# as14120_usb.net
KiCad netlist of a schematic drawn in Altium Designer
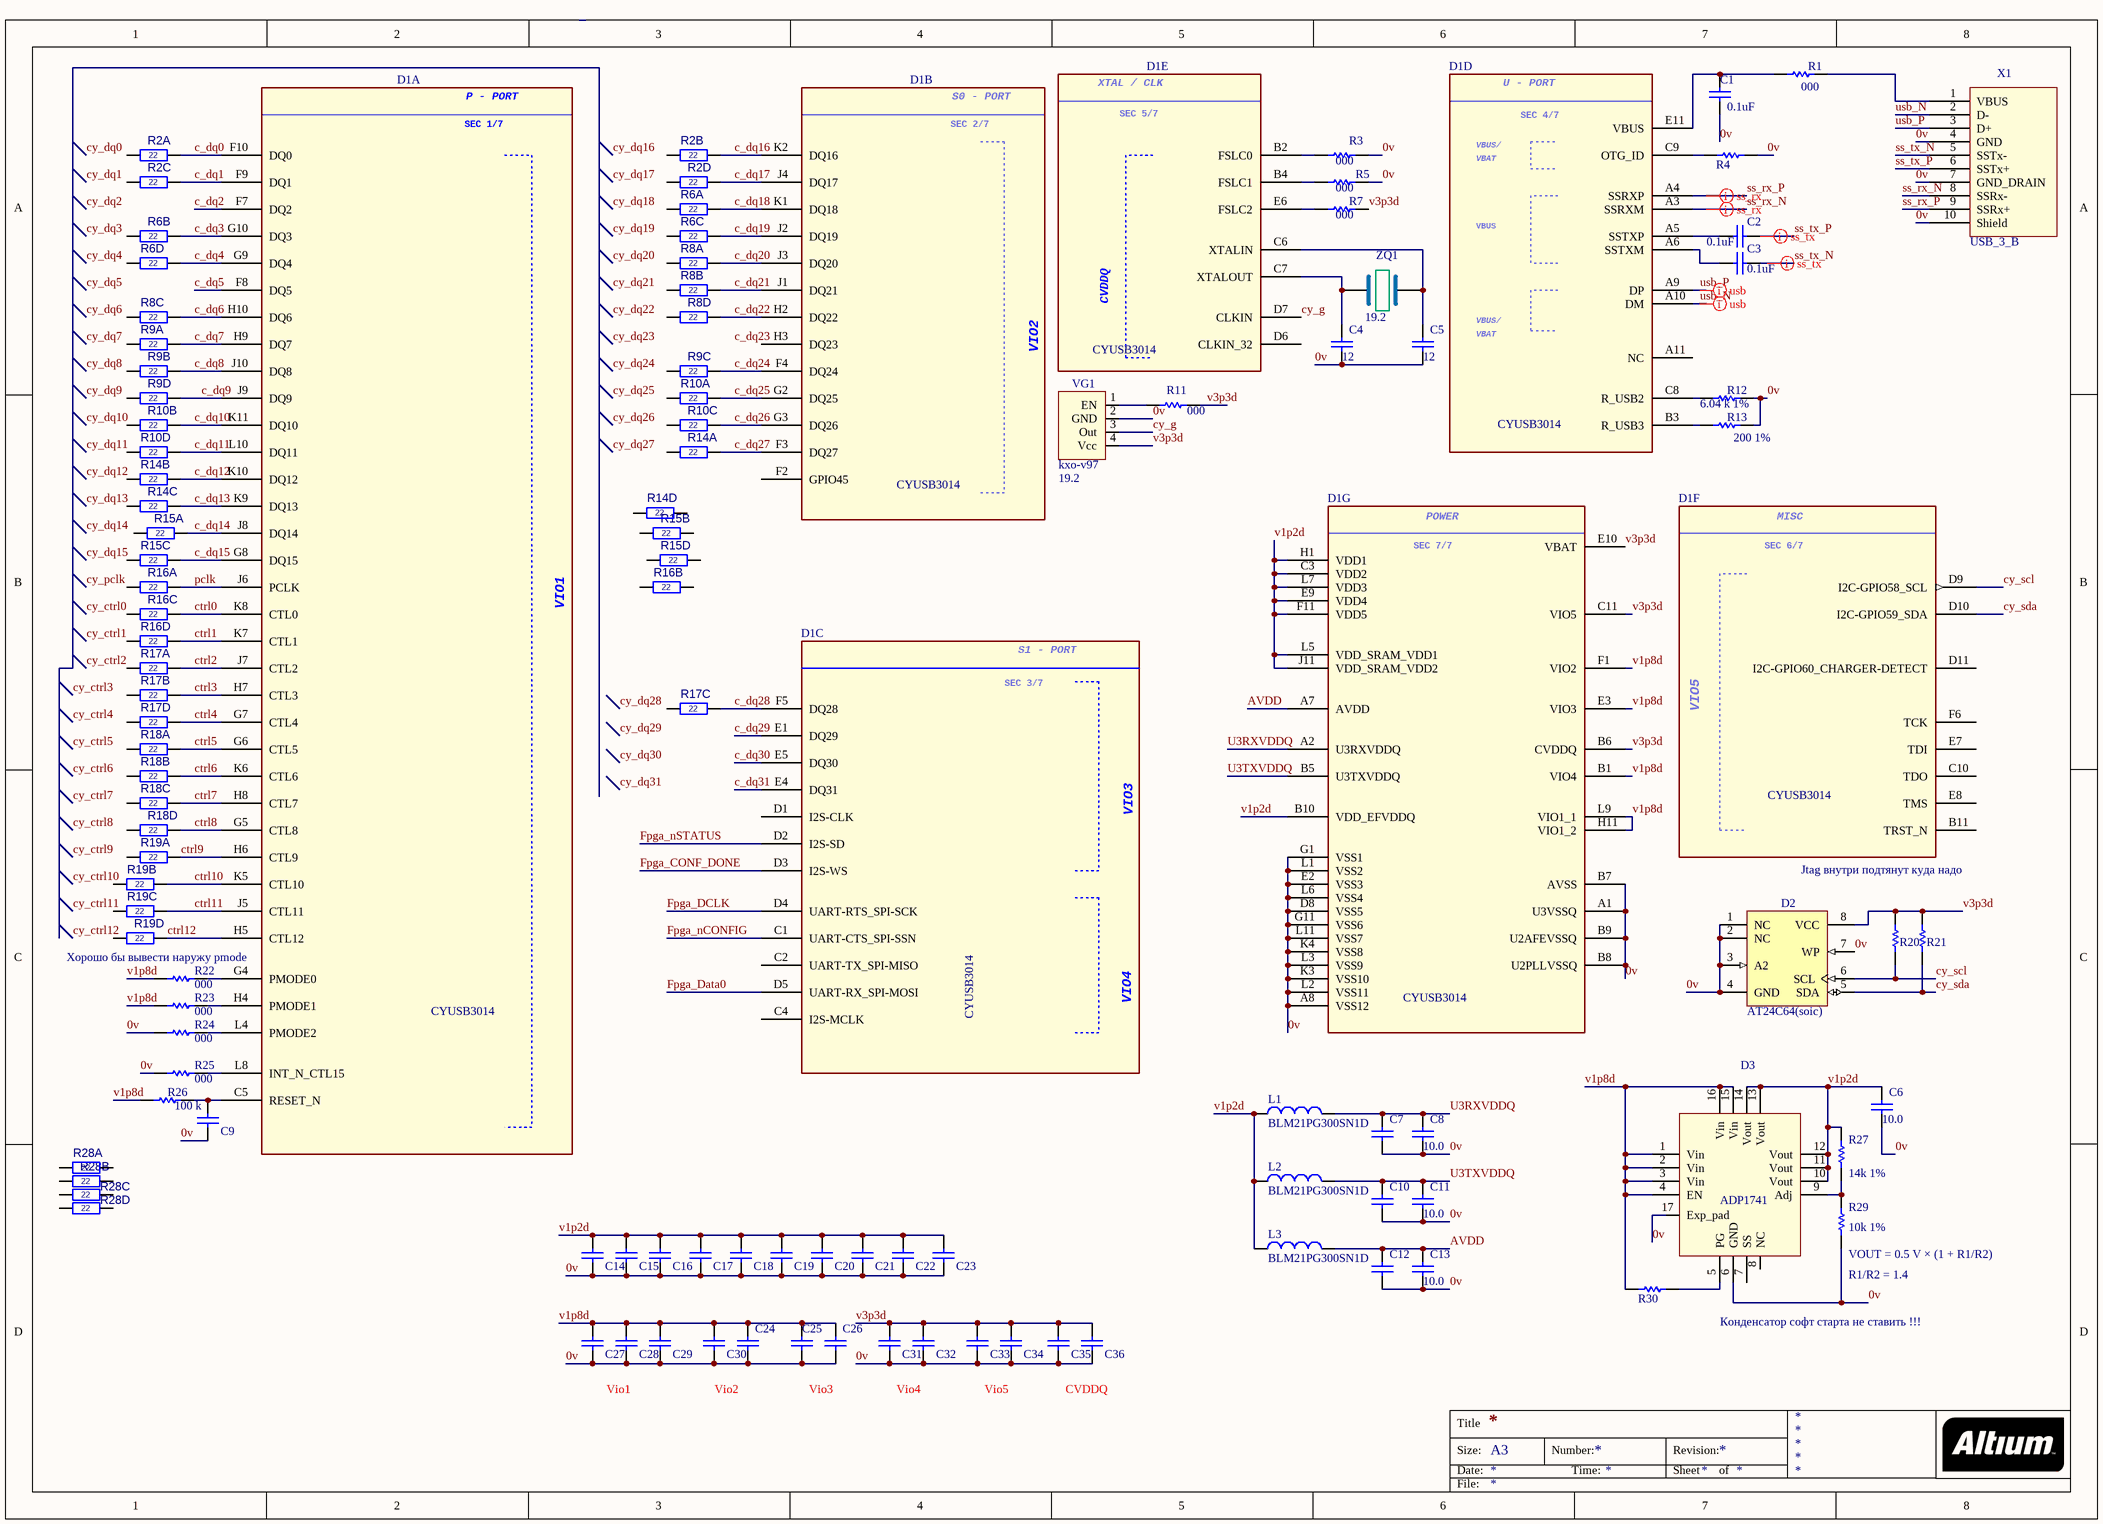
[diagram p0: as14120_usb.SchDoc]

(export (version "E")
  (design (tool "Eeschema 10.0.6"))
  (components
    (comp (ref "C1")
      (value "0.1uF")
      (footprint "CAPC0402(1005)60_M")
      (description "CAP 1uF 10V ±20% 0402 (1005 Metric) Thickness 0.6mm SMD")
      (fields (field (name "TOLERANCE") "±20%") (field (name "Comment") "CAP 1uF 10V 0402(1005)"))
      (libsource (lib "as14120") (part "CAP_0402"))
    )
    (comp (ref "C2")
      (value "0.1uF")
      (footprint "CAPC0402(1005)60_M")
      (description "CAP 1uF 10V ±20% 0402 (1005 Metric) Thickness 0.6mm SMD")
      (fields (field (name "TOLERANCE") "±20%") (field (name "Comment") "CAP 1uF 10V 0402(1005)"))
      (libsource (lib "as14120") (part "CAP_0402"))
    )
    (comp (ref "C3")
      (value "0.1uF")
      (footprint "CAPC0402(1005)60_M")
      (description "CAP 1uF 10V ±20% 0402 (1005 Metric) Thickness 0.6mm SMD")
      (fields (field (name "TOLERANCE") "±20%") (field (name "Comment") "CAP 1uF 10V 0402(1005)"))
      (libsource (lib "as14120") (part "CAP_0402"))
    )
    (comp (ref "C4")
      (value "12")
      (footprint "CAPC0805(2012)100_N")
      (fields (field (name "Comment") "CAP_0805"))
      (libsource (lib "as14120") (part "CAP_0805"))
    )
    (comp (ref "C5")
      (value "12")
      (footprint "CAPC0805(2012)100_N")
      (fields (field (name "Comment") "CAP_0805"))
      (libsource (lib "as14120") (part "CAP_0805"))
    )
    (comp (ref "C6")
      (value "10.0")
      (footprint "CAPC0805(2012)100_N")
      (fields (field (name "Comment") "CAP_0805"))
      (libsource (lib "as14120") (part "CAP_0805"))
    )
    (comp (ref "C7")
      (value "CAP 1uF 10V 0402(1005)")
      (footprint "CAPC0402(1005)60_M")
      (description "CAP 1uF 10V ±20% 0402 (1005 Metric) Thickness 0.6mm SMD")
      (fields (field (name "TOLERANCE") "±20%"))
      (libsource (lib "as14120") (part "CAP_0402"))
    )
    (comp (ref "C8")
      (value "10.0")
      (footprint "CAPC0805(2012)100_N")
      (fields (field (name "Comment") "CAP_0805"))
      (libsource (lib "as14120") (part "CAP_0805"))
    )
    (comp (ref "C9")
      (value "CAP 1uF 10V 0402(1005)")
      (footprint "CAPC0402(1005)60_M")
      (description "CAP 1uF 10V ±20% 0402 (1005 Metric) Thickness 0.6mm SMD")
      (fields (field (name "TOLERANCE") "±20%"))
      (libsource (lib "as14120") (part "CAP_0402"))
    )
    (comp (ref "C10")
      (value "CAP 1uF 10V 0402(1005)")
      (footprint "CAPC0402(1005)60_M")
      (description "CAP 1uF 10V ±20% 0402 (1005 Metric) Thickness 0.6mm SMD")
      (fields (field (name "TOLERANCE") "±20%"))
      (libsource (lib "as14120") (part "CAP_0402"))
    )
    (comp (ref "C11")
      (value "10.0")
      (footprint "CAPC0805(2012)100_N")
      (fields (field (name "Comment") "CAP_0805"))
      (libsource (lib "as14120") (part "CAP_0805"))
    )
    (comp (ref "C12")
      (value "CAP 1uF 10V 0402(1005)")
      (footprint "CAPC0402(1005)60_M")
      (description "CAP 1uF 10V ±20% 0402 (1005 Metric) Thickness 0.6mm SMD")
      (fields (field (name "TOLERANCE") "±20%"))
      (libsource (lib "as14120") (part "CAP_0402"))
    )
    (comp (ref "C13")
      (value "10.0")
      (footprint "CAPC0805(2012)100_N")
      (fields (field (name "Comment") "CAP_0805"))
      (libsource (lib "as14120") (part "CAP_0805"))
    )
    (comp (ref "C14")
      (value "CAP 1uF 10V 0402(1005)")
      (footprint "CAPC0402(1005)60_M")
      (description "CAP 1uF 10V ±20% 0402 (1005 Metric) Thickness 0.6mm SMD")
      (fields (field (name "TOLERANCE") "±20%"))
      (libsource (lib "as14120") (part "CAP_0402"))
    )
    (comp (ref "C15")
      (value "CAP 1uF 10V 0402(1005)")
      (footprint "CAPC0402(1005)60_M")
      (description "CAP 1uF 10V ±20% 0402 (1005 Metric) Thickness 0.6mm SMD")
      (fields (field (name "TOLERANCE") "±20%"))
      (libsource (lib "as14120") (part "CAP_0402"))
    )
    (comp (ref "C16")
      (value "CAP 1uF 10V 0402(1005)")
      (footprint "CAPC0402(1005)60_M")
      (description "CAP 1uF 10V ±20% 0402 (1005 Metric) Thickness 0.6mm SMD")
      (fields (field (name "TOLERANCE") "±20%"))
      (libsource (lib "as14120") (part "CAP_0402"))
    )
    (comp (ref "C17")
      (value "CAP 1uF 10V 0402(1005)")
      (footprint "CAPC0402(1005)60_M")
      (description "CAP 1uF 10V ±20% 0402 (1005 Metric) Thickness 0.6mm SMD")
      (fields (field (name "TOLERANCE") "±20%"))
      (libsource (lib "as14120") (part "CAP_0402"))
    )
    (comp (ref "C18")
      (value "CAP 1uF 10V 0402(1005)")
      (footprint "CAPC0402(1005)60_M")
      (description "CAP 1uF 10V ±20% 0402 (1005 Metric) Thickness 0.6mm SMD")
      (fields (field (name "TOLERANCE") "±20%"))
      (libsource (lib "as14120") (part "CAP_0402"))
    )
    (comp (ref "C19")
      (value "CAP 1uF 10V 0402(1005)")
      (footprint "CAPC0402(1005)60_M")
      (description "CAP 1uF 10V ±20% 0402 (1005 Metric) Thickness 0.6mm SMD")
      (fields (field (name "TOLERANCE") "±20%"))
      (libsource (lib "as14120") (part "CAP_0402"))
    )
    (comp (ref "C20")
      (value "CAP 1uF 10V 0402(1005)")
      (footprint "CAPC0402(1005)60_M")
      (description "CAP 1uF 10V ±20% 0402 (1005 Metric) Thickness 0.6mm SMD")
      (fields (field (name "TOLERANCE") "±20%"))
      (libsource (lib "as14120") (part "CAP_0402"))
    )
    (comp (ref "C21")
      (value "CAP 1uF 10V 0402(1005)")
      (footprint "CAPC0402(1005)60_M")
      (description "CAP 1uF 10V ±20% 0402 (1005 Metric) Thickness 0.6mm SMD")
      (fields (field (name "TOLERANCE") "±20%"))
      (libsource (lib "as14120") (part "CAP_0402"))
    )
    (comp (ref "C22")
      (value "CAP 1uF 10V 0402(1005)")
      (footprint "CAPC0402(1005)60_M")
      (description "CAP 1uF 10V ±20% 0402 (1005 Metric) Thickness 0.6mm SMD")
      (fields (field (name "TOLERANCE") "±20%"))
      (libsource (lib "as14120") (part "CAP_0402"))
    )
    (comp (ref "C23")
      (value "CAP 1uF 10V 0402(1005)")
      (footprint "CAPC0402(1005)60_M")
      (description "CAP 1uF 10V ±20% 0402 (1005 Metric) Thickness 0.6mm SMD")
      (fields (field (name "TOLERANCE") "±20%"))
      (libsource (lib "as14120") (part "CAP_0402"))
    )
    (comp (ref "C24")
      (value "CAP 1uF 10V 0402(1005)")
      (footprint "CAPC0402(1005)60_M")
      (description "CAP 1uF 10V ±20% 0402 (1005 Metric) Thickness 0.6mm SMD")
      (fields (field (name "TOLERANCE") "±20%"))
      (libsource (lib "as14120") (part "CAP_0402"))
    )
    (comp (ref "C25")
      (value "CAP 1uF 10V 0402(1005)")
      (footprint "CAPC0402(1005)60_M")
      (description "CAP 1uF 10V ±20% 0402 (1005 Metric) Thickness 0.6mm SMD")
      (fields (field (name "TOLERANCE") "±20%"))
      (libsource (lib "as14120") (part "CAP_0402"))
    )
    (comp (ref "C26")
      (value "CAP 1uF 10V 0402(1005)")
      (footprint "CAPC0402(1005)60_M")
      (description "CAP 1uF 10V ±20% 0402 (1005 Metric) Thickness 0.6mm SMD")
      (fields (field (name "TOLERANCE") "±20%"))
      (libsource (lib "as14120") (part "CAP_0402"))
    )
    (comp (ref "C27")
      (value "CAP 1uF 10V 0402(1005)")
      (footprint "CAPC0402(1005)60_M")
      (description "CAP 1uF 10V ±20% 0402 (1005 Metric) Thickness 0.6mm SMD")
      (fields (field (name "TOLERANCE") "±20%"))
      (libsource (lib "as14120") (part "CAP_0402"))
    )
    (comp (ref "C28")
      (value "CAP 1uF 10V 0402(1005)")
      (footprint "CAPC0402(1005)60_M")
      (description "CAP 1uF 10V ±20% 0402 (1005 Metric) Thickness 0.6mm SMD")
      (fields (field (name "TOLERANCE") "±20%"))
      (libsource (lib "as14120") (part "CAP_0402"))
    )
    (comp (ref "C29")
      (value "CAP 1uF 10V 0402(1005)")
      (footprint "CAPC0402(1005)60_M")
      (description "CAP 1uF 10V ±20% 0402 (1005 Metric) Thickness 0.6mm SMD")
      (fields (field (name "TOLERANCE") "±20%"))
      (libsource (lib "as14120") (part "CAP_0402"))
    )
    (comp (ref "C30")
      (value "CAP 1uF 10V 0402(1005)")
      (footprint "CAPC0402(1005)60_M")
      (description "CAP 1uF 10V ±20% 0402 (1005 Metric) Thickness 0.6mm SMD")
      (fields (field (name "TOLERANCE") "±20%"))
      (libsource (lib "as14120") (part "CAP_0402"))
    )
    (comp (ref "C31")
      (value "CAP 1uF 10V 0402(1005)")
      (footprint "CAPC0402(1005)60_M")
      (description "CAP 1uF 10V ±20% 0402 (1005 Metric) Thickness 0.6mm SMD")
      (fields (field (name "TOLERANCE") "±20%"))
      (libsource (lib "as14120") (part "CAP_0402"))
    )
    (comp (ref "C32")
      (value "CAP 1uF 10V 0402(1005)")
      (footprint "CAPC0402(1005)60_M")
      (description "CAP 1uF 10V ±20% 0402 (1005 Metric) Thickness 0.6mm SMD")
      (fields (field (name "TOLERANCE") "±20%"))
      (libsource (lib "as14120") (part "CAP_0402"))
    )
    (comp (ref "C33")
      (value "CAP 1uF 10V 0402(1005)")
      (footprint "CAPC0402(1005)60_M")
      (description "CAP 1uF 10V ±20% 0402 (1005 Metric) Thickness 0.6mm SMD")
      (fields (field (name "TOLERANCE") "±20%"))
      (libsource (lib "as14120") (part "CAP_0402"))
    )
    (comp (ref "C34")
      (value "CAP 1uF 10V 0402(1005)")
      (footprint "CAPC0402(1005)60_M")
      (description "CAP 1uF 10V ±20% 0402 (1005 Metric) Thickness 0.6mm SMD")
      (fields (field (name "TOLERANCE") "±20%"))
      (libsource (lib "as14120") (part "CAP_0402"))
    )
    (comp (ref "C35")
      (value "CAP 1uF 10V 0402(1005)")
      (footprint "CAPC0402(1005)60_M")
      (description "CAP 1uF 10V ±20% 0402 (1005 Metric) Thickness 0.6mm SMD")
      (fields (field (name "TOLERANCE") "±20%"))
      (libsource (lib "as14120") (part "CAP_0402"))
    )
    (comp (ref "C36")
      (value "CAP 1uF 10V 0402(1005)")
      (footprint "CAPC0402(1005)60_M")
      (description "CAP 1uF 10V ±20% 0402 (1005 Metric) Thickness 0.6mm SMD")
      (fields (field (name "TOLERANCE") "±20%"))
      (libsource (lib "as14120") (part "CAP_0402"))
    )
    (comp (ref "D1")
      (value "CYUSB3014")
      (footprint "BGA121C80P11X11")
      (libsource (lib "as14120") (part "CYUSB3014-BZXC"))
    )
    (comp (ref "D2")
      (value "AT24C64(soic)")
      (footprint "8S1_N")
      (libsource (lib "Atmel Serial EEPROM") (part "AT24C08BN-SP25-T"))
    )
    (comp (ref "D3") (value "ADP1741") (footprint "CP-16-4_N") (libsource (lib "as14120") (part "ADP1741")))
    (comp (ref "L1")
      (value "BLM21PG300SN1D")
      (footprint "CAPC0805(2012)100_N")
      (libsource (lib "as14120") (part "Ferrite_beat"))
    )
    (comp (ref "L2")
      (value "BLM21PG300SN1D")
      (footprint "CAPC0805(2012)100_N")
      (libsource (lib "as14120") (part "Ferrite_beat"))
    )
    (comp (ref "L3")
      (value "BLM21PG300SN1D")
      (footprint "CAPC0805(2012)100_N")
      (libsource (lib "as14120") (part "Ferrite_beat"))
    )
    (comp (ref "R1")
      (value "000")
      (footprint "RESC0805(2012)_L")
      (description "1K 0.125W 1% 0805 (2012 Metric)  SMD")
      (fields (field (name "TOLERANCE") "1 %") (field (name "POWER") "0.125 W"))
      (libsource (lib "as14120") (part "RES_0805"))
    )
    (comp (ref "R2")
      (value "22")
      (footprint "CAY16")
      (description "RES_CAY16")
      (libsource (lib "") (part "RES_CAY16_10"))
    )
    (comp (ref "R3")
      (value "000")
      (footprint "RESC0603(1608)_L")
      (description "1K 0.1W 5% 0603 (1608 Metric)  SMD")
      (fields (field (name "TOLERANCE") "5 %") (field (name "POWER") "0.1 W"))
      (libsource (lib "as14120") (part "RES_0603"))
    )
    (comp (ref "R4")
      (value "???")
      (footprint "RESC0603(1608)_L")
      (description "1K 0.1W 5% 0603 (1608 Metric)  SMD")
      (fields (field (name "TOLERANCE") "5 %") (field (name "POWER") "0.1 W"))
      (libsource (lib "as14120") (part "RES_0603"))
    )
    (comp (ref "R5")
      (value "000")
      (footprint "RESC0603(1608)_L")
      (description "1K 0.1W 5% 0603 (1608 Metric)  SMD")
      (fields (field (name "TOLERANCE") "5 %") (field (name "POWER") "0.1 W"))
      (libsource (lib "as14120") (part "RES_0603"))
    )
    (comp (ref "R6")
      (value "22")
      (footprint "CAY16")
      (description "RES_CAY16")
      (libsource (lib "alexsb") (part "RES_CAY16"))
    )
    (comp (ref "R7")
      (value "000")
      (footprint "RESC0603(1608)_L")
      (description "1K 0.1W 5% 0603 (1608 Metric)  SMD")
      (fields (field (name "TOLERANCE") "5 %") (field (name "POWER") "0.1 W"))
      (libsource (lib "as14120") (part "RES_0603"))
    )
    (comp (ref "R8")
      (value "22")
      (footprint "CAY16")
      (description "RES_CAY16")
      (libsource (lib "") (part "RES_CAY16_4"))
    )
    (comp (ref "R9")
      (value "22")
      (footprint "CAY16")
      (description "RES_CAY16")
      (libsource (lib "alexsb") (part "RES_CAY16"))
    )
    (comp (ref "R10")
      (value "22")
      (footprint "CAY16")
      (description "RES_CAY16")
      (libsource (lib "") (part "RES_CAY16_5"))
    )
    (comp (ref "R11")
      (value "000")
      (footprint "RESC0603(1608)_L")
      (description "1K 0.1W 5% 0603 (1608 Metric)  SMD")
      (fields (field (name "TOLERANCE") "5 %") (field (name "POWER") "0.1 W"))
      (libsource (lib "as14120") (part "RES_0603"))
    )
    (comp (ref "R12")
      (value "6.04 k 1%")
      (footprint "RESC0805(2012)_L")
      (description "1K 0.125W 1% 0805 (2012 Metric)  SMD")
      (fields (field (name "TOLERANCE") "1 %") (field (name "POWER") "0.125 W"))
      (libsource (lib "as14120") (part "RES_0805"))
    )
    (comp (ref "R13")
      (value "200 1%")
      (footprint "RESC0805(2012)_L")
      (description "1K 0.125W 1% 0805 (2012 Metric)  SMD")
      (fields (field (name "TOLERANCE") "1 %") (field (name "POWER") "0.125 W"))
      (libsource (lib "as14120") (part "RES_0805"))
    )
    (comp (ref "R14")
      (value "22")
      (footprint "CAY16")
      (description "RES_CAY16")
      (libsource (lib "") (part "RES_CAY16_8"))
    )
    (comp (ref "R15")
      (value "22")
      (footprint "CAY16")
      (description "RES_CAY16")
      (libsource (lib "") (part "RES_CAY16_1"))
    )
    (comp (ref "R16")
      (value "22")
      (footprint "CAY16")
      (description "RES_CAY16")
      (libsource (lib "") (part "RES_CAY16_5"))
    )
    (comp (ref "R17")
      (value "22")
      (footprint "CAY16")
      (description "RES_CAY16")
      (libsource (lib "") (part "RES_CAY16_7"))
    )
    (comp (ref "R18")
      (value "22")
      (footprint "CAY16")
      (description "RES_CAY16")
      (libsource (lib "") (part "RES_CAY16_3"))
    )
    (comp (ref "R19")
      (value "22")
      (footprint "CAY16")
      (description "RES_CAY16")
      (libsource (lib "alexsb") (part "RES_CAY16"))
    )
    (comp (ref "R20")
      (value "1K 5% 0603(1608)")
      (footprint "RESC0603(1608)_L")
      (description "1K 0.1W 5% 0603 (1608 Metric)  SMD")
      (fields (field (name "TOLERANCE") "5 %") (field (name "POWER") "0.1 W"))
      (libsource (lib "as14120") (part "RES_0603"))
    )
    (comp (ref "R21")
      (value "1K 5% 0603(1608)")
      (footprint "RESC0603(1608)_L")
      (description "1K 0.1W 5% 0603 (1608 Metric)  SMD")
      (fields (field (name "TOLERANCE") "5 %") (field (name "POWER") "0.1 W"))
      (libsource (lib "as14120") (part "RES_0603"))
    )
    (comp (ref "R22")
      (value "000")
      (footprint "RESC0603(1608)_L")
      (description "1K 0.1W 5% 0603 (1608 Metric)  SMD")
      (fields (field (name "TOLERANCE") "5 %") (field (name "POWER") "0.1 W"))
      (libsource (lib "as14120") (part "RES_0603"))
    )
    (comp (ref "R23")
      (value "000")
      (footprint "RESC0603(1608)_L")
      (description "1K 0.1W 5% 0603 (1608 Metric)  SMD")
      (fields (field (name "TOLERANCE") "5 %") (field (name "POWER") "0.1 W"))
      (libsource (lib "as14120") (part "RES_0603"))
    )
    (comp (ref "R24")
      (value "000")
      (footprint "RESC0603(1608)_L")
      (description "1K 0.1W 5% 0603 (1608 Metric)  SMD")
      (fields (field (name "TOLERANCE") "5 %") (field (name "POWER") "0.1 W"))
      (libsource (lib "as14120") (part "RES_0603"))
    )
    (comp (ref "R25")
      (value "000")
      (footprint "RESC0603(1608)_L")
      (description "1K 0.1W 5% 0603 (1608 Metric)  SMD")
      (fields (field (name "TOLERANCE") "5 %") (field (name "POWER") "0.1 W"))
      (libsource (lib "as14120") (part "RES_0603"))
    )
    (comp (ref "R26")
      (value "100 k")
      (footprint "RESC0603(1608)_L")
      (description "1K 0.1W 5% 0603 (1608 Metric)  SMD")
      (fields (field (name "TOLERANCE") "5 %") (field (name "POWER") "0.1 W"))
      (libsource (lib "as14120") (part "RES_0603"))
    )
    (comp (ref "R27")
      (value "14k 1%")
      (footprint "RESC0805(2012)_L")
      (description "1K 0.125W 1% 0805 (2012 Metric)  SMD")
      (fields (field (name "TOLERANCE") "1 %") (field (name "POWER") "0.125 W"))
      (libsource (lib "as14120") (part "RES_0805"))
    )
    (comp (ref "R28")
      (value "22")
      (footprint "CAY16")
      (description "RES_CAY16")
      (libsource (lib "") (part "RES_CAY16_1"))
    )
    (comp (ref "R29")
      (value "10k 1%")
      (footprint "RESC0805(2012)_L")
      (description "1K 0.125W 1% 0805 (2012 Metric)  SMD")
      (fields (field (name "TOLERANCE") "1 %") (field (name "POWER") "0.125 W"))
      (libsource (lib "as14120") (part "RES_0805"))
    )
    (comp (ref "R30")
      (value "1K 5% 0603(1608)")
      (footprint "RESC0603(1608)_L")
      (description "1K 0.1W 5% 0603 (1608 Metric)  SMD")
      (fields (field (name "TOLERANCE") "5 %") (field (name "POWER") "0.1 W"))
      (libsource (lib "as14120") (part "RES_0603"))
    )
    (comp (ref "VG1")
      (value "kxo-v97")
      (footprint "kxo-v97")
      (fields (field (name "ALTIUM_VALUE") "19.2"))
      (libsource (lib "as14120") (part "kxo-v97"))
    )
    (comp (ref "X1") (value "USB_3_B") (footprint "USB3_B") (libsource (lib "as14120") (part "USB_3_B")))
    (comp (ref "ZQ1")
      (value "19.2")
      (footprint "BCY-W2/E4.7")
      (fields (field (name "Comment") "Resonator"))
      (libsource (lib "as14120") (part "Resonator"))
    )
  )
  (nets
    (net (code "1") (name "/0v") (class "Default")
      (node (ref "C1") (pin "2") (pinfunction "2_2") (pintype "passive"))
      (node (ref "C10") (pin "1") (pinfunction "1_1") (pintype "passive"))
      (node (ref "C11") (pin "1") (pinfunction "1_1") (pintype "passive"))
      (node (ref "C12") (pin "1") (pinfunction "1_1") (pintype "passive"))
      (node (ref "C13") (pin "1") (pinfunction "1_1") (pintype "passive"))
      (node (ref "C14") (pin "1") (pinfunction "1_1") (pintype "passive"))
      (node (ref "C15") (pin "1") (pinfunction "1_1") (pintype "passive"))
      (node (ref "C16") (pin "1") (pinfunction "1_1") (pintype "passive"))
      (node (ref "C17") (pin "1") (pinfunction "1_1") (pintype "passive"))
      (node (ref "C18") (pin "1") (pinfunction "1_1") (pintype "passive"))
      (node (ref "C19") (pin "1") (pinfunction "1_1") (pintype "passive"))
      (node (ref "C20") (pin "1") (pinfunction "1_1") (pintype "passive"))
      (node (ref "C21") (pin "1") (pinfunction "1_1") (pintype "passive"))
      (node (ref "C22") (pin "1") (pinfunction "1_1") (pintype "passive"))
      (node (ref "C23") (pin "1") (pinfunction "1_1") (pintype "passive"))
      (node (ref "C24") (pin "1") (pinfunction "1_1") (pintype "passive"))
      (node (ref "C25") (pin "1") (pinfunction "1_1") (pintype "passive"))
      (node (ref "C26") (pin "1") (pinfunction "1_1") (pintype "passive"))
      (node (ref "C27") (pin "1") (pinfunction "1_1") (pintype "passive"))
      (node (ref "C28") (pin "1") (pinfunction "1_1") (pintype "passive"))
      (node (ref "C29") (pin "1") (pinfunction "1_1") (pintype "passive"))
      (node (ref "C30") (pin "1") (pinfunction "1_1") (pintype "passive"))
      (node (ref "C31") (pin "1") (pinfunction "1_1") (pintype "passive"))
      (node (ref "C32") (pin "1") (pinfunction "1_1") (pintype "passive"))
      (node (ref "C33") (pin "1") (pinfunction "1_1") (pintype "passive"))
      (node (ref "C34") (pin "1") (pinfunction "1_1") (pintype "passive"))
      (node (ref "C35") (pin "1") (pinfunction "1_1") (pintype "passive"))
      (node (ref "C36") (pin "1") (pinfunction "1_1") (pintype "passive"))
      (node (ref "C4") (pin "1") (pinfunction "1_1") (pintype "passive"))
      (node (ref "C5") (pin "1") (pinfunction "1_1") (pintype "passive"))
      (node (ref "C6") (pin "1") (pinfunction "1_1") (pintype "passive"))
      (node (ref "C7") (pin "1") (pinfunction "1_1") (pintype "passive"))
      (node (ref "C8") (pin "1") (pinfunction "1_1") (pintype "passive"))
      (node (ref "C9") (pin "1") (pinfunction "1_1") (pintype "passive"))
      (node (ref "D1") (pin "A1") (pinfunction "U3VSSQ_A1") (pintype "passive"))
      (node (ref "D1") (pin "A8") (pinfunction "VSS12_A8") (pintype "passive"))
      (node (ref "D1") (pin "B7") (pinfunction "AVSS_B7") (pintype "passive"))
      (node (ref "D1") (pin "B8") (pinfunction "U2PLLVSSQ_B8") (pintype "passive"))
      (node (ref "D1") (pin "B9") (pinfunction "U2AFEVSSQ_B9") (pintype "passive"))
      (node (ref "D1") (pin "D8") (pinfunction "VSS5_D8") (pintype "passive"))
      (node (ref "D1") (pin "E2") (pinfunction "VSS3_E2") (pintype "passive"))
      (node (ref "D1") (pin "G1") (pinfunction "VSS1_G1") (pintype "passive"))
      (node (ref "D1") (pin "G11") (pinfunction "VSS6_G11") (pintype "passive"))
      (node (ref "D1") (pin "K3") (pinfunction "VSS10_K3") (pintype "passive"))
      (node (ref "D1") (pin "K4") (pinfunction "VSS8_K4") (pintype "passive"))
      (node (ref "D1") (pin "L1") (pinfunction "VSS2_L1") (pintype "passive"))
      (node (ref "D1") (pin "L11") (pinfunction "VSS7_L11") (pintype "passive"))
      (node (ref "D1") (pin "L2") (pinfunction "VSS11_L2") (pintype "passive"))
      (node (ref "D1") (pin "L3") (pinfunction "VSS9_L3") (pintype "passive"))
      (node (ref "D1") (pin "L6") (pinfunction "VSS4_L6") (pintype "passive"))
      (node (ref "D2") (pin "1") (pinfunction "NC_1") (pintype "passive"))
      (node (ref "D2") (pin "2") (pinfunction "NC_2") (pintype "passive"))
      (node (ref "D2") (pin "3") (pinfunction "A2_3") (pintype "input"))
      (node (ref "D2") (pin "4") (pinfunction "GND_4") (pintype "power_in"))
      (node (ref "D2") (pin "7") (pinfunction "WP_7") (pintype "input"))
      (node (ref "D3") (pin "17") (pinfunction "Exp_pad_17") (pintype "passive"))
      (node (ref "D3") (pin "6") (pinfunction "GND_6") (pintype "passive"))
      (node (ref "R12") (pin "2") (pinfunction "2_2") (pintype "passive"))
      (node (ref "R13") (pin "2") (pinfunction "2_2") (pintype "passive"))
      (node (ref "R24") (pin "2") (pinfunction "2_2") (pintype "passive"))
      (node (ref "R25") (pin "2") (pinfunction "2_2") (pintype "passive"))
      (node (ref "R29") (pin "1") (pinfunction "1_1") (pintype "passive"))
      (node (ref "R3") (pin "1") (pinfunction "1_1") (pintype "passive"))
      (node (ref "R4") (pin "2") (pinfunction "2_2") (pintype "passive"))
      (node (ref "R5") (pin "1") (pinfunction "1_1") (pintype "passive"))
      (node (ref "VG1") (pin "2") (pinfunction "GND_2") (pintype "passive"))
      (node (ref "X1") (pin "10") (pinfunction "Shield_10") (pintype "passive"))
      (node (ref "X1") (pin "4") (pinfunction "GND_4") (pintype "passive"))
      (node (ref "X1") (pin "7") (pinfunction "GND_DRAIN_7") (pintype "passive"))
    )
    (net (code "2") (name "/AVDD") (class "Default")
      (node (ref "C12") (pin "2") (pinfunction "2_2") (pintype "passive"))
      (node (ref "C13") (pin "2") (pinfunction "2_2") (pintype "passive"))
      (node (ref "D1") (pin "A7") (pinfunction "AVDD_A7") (pintype "passive"))
      (node (ref "L3") (pin "2") (pinfunction "2_2") (pintype "passive"))
    )
    (net (code "3") (name "/Fpga_CONF_DONE") (class "Default")
      (node (ref "D1") (pin "D3") (pinfunction "I2S-WS_D3") (pintype "passive"))
    )
    (net (code "4") (name "/Fpga_DCLK") (class "Default")
      (node (ref "D1") (pin "D4") (pinfunction "UART-RTS_SPI-SCK_D4") (pintype "passive"))
    )
    (net (code "5") (name "/Fpga_Data0") (class "Default")
      (node (ref "D1") (pin "D5") (pinfunction "UART-RX_SPI-MOSI_D5") (pintype "passive"))
    )
    (net (code "6") (name "/Fpga_nCONFIG") (class "Default")
      (node (ref "D1") (pin "C1") (pinfunction "UART-CTS_SPI-SSN_C1") (pintype "passive"))
    )
    (net (code "7") (name "/Fpga_nSTATUS") (class "Default")
      (node (ref "D1") (pin "D2") (pinfunction "I2S-SD_D2") (pintype "passive"))
    )
    (net (code "8") (name "/U3RXVDDQ") (class "Default")
      (node (ref "C7") (pin "2") (pinfunction "2_2") (pintype "passive"))
      (node (ref "C8") (pin "2") (pinfunction "2_2") (pintype "passive"))
      (node (ref "D1") (pin "A2") (pinfunction "U3RXVDDQ_A2") (pintype "passive"))
      (node (ref "L1") (pin "2") (pinfunction "2_2") (pintype "passive"))
    )
    (net (code "9") (name "/U3TXVDDQ") (class "Default")
      (node (ref "C10") (pin "2") (pinfunction "2_2") (pintype "passive"))
      (node (ref "C11") (pin "2") (pinfunction "2_2") (pintype "passive"))
      (node (ref "D1") (pin "B5") (pinfunction "U3TXVDDQ_B5") (pintype "passive"))
      (node (ref "L2") (pin "2") (pinfunction "2_2") (pintype "passive"))
    )
    (net (code "10") (name "/c_dq0") (class "Default")
      (node (ref "D1") (pin "F10") (pinfunction "DQ0_F10") (pintype "passive"))
      (node (ref "R2") (pin "8") (pinfunction "2_8") (pintype "passive"))
    )
    (net (code "11") (name "/c_dq1") (class "Default")
      (node (ref "D1") (pin "F9") (pinfunction "DQ1_F9") (pintype "passive"))
      (node (ref "R2") (pin "6") (pinfunction "2_6") (pintype "passive"))
    )
    (net (code "12") (name "/c_dq2") (class "Default")
      (node (ref "D1") (pin "F7") (pinfunction "DQ2_F7") (pintype "passive"))
    )
    (net (code "13") (name "/c_dq3") (class "Default")
      (node (ref "D1") (pin "G10") (pinfunction "DQ3_G10") (pintype "passive"))
      (node (ref "R6") (pin "7") (pinfunction "2_7") (pintype "passive"))
    )
    (net (code "14") (name "/c_dq4") (class "Default")
      (node (ref "D1") (pin "G9") (pinfunction "DQ4_G9") (pintype "passive"))
      (node (ref "R6") (pin "8") (pinfunction "2_8") (pintype "passive"))
    )
    (net (code "15") (name "/c_dq5") (class "Default")
      (node (ref "D1") (pin "F8") (pinfunction "DQ5_F8") (pintype "passive"))
    )
    (net (code "16") (name "/c_dq6") (class "Default")
      (node (ref "D1") (pin "H10") (pinfunction "DQ6_H10") (pintype "passive"))
      (node (ref "R8") (pin "6") (pinfunction "2_6") (pintype "passive"))
    )
    (net (code "17") (name "/c_dq7") (class "Default")
      (node (ref "D1") (pin "H9") (pinfunction "DQ7_H9") (pintype "passive"))
      (node (ref "R9") (pin "8") (pinfunction "2_8") (pintype "passive"))
    )
    (net (code "18") (name "/c_dq8") (class "Default")
      (node (ref "D1") (pin "J10") (pinfunction "DQ8_J10") (pintype "passive"))
      (node (ref "R9") (pin "7") (pinfunction "2_7") (pintype "passive"))
    )
    (net (code "19") (name "/c_dq9") (class "Default")
      (node (ref "D1") (pin "J9") (pinfunction "DQ9_J9") (pintype "passive"))
      (node (ref "R9") (pin "8") (pinfunction "2_8") (pintype "passive"))
    )
    (net (code "20") (name "/c_dq10") (class "Default")
      (node (ref "D1") (pin "K11") (pinfunction "DQ10_K11") (pintype "passive"))
      (node (ref "R10") (pin "7") (pinfunction "2_7") (pintype "passive"))
    )
    (net (code "21") (name "/c_dq11") (class "Default")
      (node (ref "D1") (pin "L10") (pinfunction "DQ11_L10") (pintype "passive"))
      (node (ref "R10") (pin "8") (pinfunction "2_8") (pintype "passive"))
    )
    (net (code "22") (name "/c_dq12") (class "Default")
      (node (ref "D1") (pin "K10") (pinfunction "DQ12_K10") (pintype "passive"))
      (node (ref "R14") (pin "7") (pinfunction "2_7") (pintype "passive"))
    )
    (net (code "23") (name "/c_dq13") (class "Default")
      (node (ref "D1") (pin "K9") (pinfunction "DQ13_K9") (pintype "passive"))
      (node (ref "R14") (pin "6") (pinfunction "2_6") (pintype "passive"))
    )
    (net (code "24") (name "/c_dq14") (class "Default")
      (node (ref "D1") (pin "J8") (pinfunction "DQ14_J8") (pintype "passive"))
      (node (ref "R15") (pin "8") (pinfunction "2_8") (pintype "passive"))
    )
    (net (code "25") (name "/c_dq15") (class "Default")
      (node (ref "D1") (pin "G8") (pinfunction "DQ15_G8") (pintype "passive"))
      (node (ref "R15") (pin "7") (pinfunction "2_7") (pintype "passive"))
    )
    (net (code "26") (name "/c_dq16") (class "Default")
      (node (ref "D1") (pin "K2") (pinfunction "DQ16_K2") (pintype "passive"))
      (node (ref "R2") (pin "7") (pinfunction "2_7") (pintype "passive"))
    )
    (net (code "27") (name "/c_dq17") (class "Default")
      (node (ref "D1") (pin "J4") (pinfunction "DQ17_J4") (pintype "passive"))
      (node (ref "R2") (pin "5") (pinfunction "2_5") (pintype "passive"))
    )
    (net (code "28") (name "/c_dq18") (class "Default")
      (node (ref "D1") (pin "K1") (pinfunction "DQ18_K1") (pintype "passive"))
      (node (ref "R6") (pin "8") (pinfunction "2_8") (pintype "passive"))
    )
    (net (code "29") (name "/c_dq19") (class "Default")
      (node (ref "D1") (pin "J2") (pinfunction "DQ19_J2") (pintype "passive"))
      (node (ref "R6") (pin "6") (pinfunction "2_6") (pintype "passive"))
    )
    (net (code "30") (name "/c_dq20") (class "Default")
      (node (ref "D1") (pin "J3") (pinfunction "DQ20_J3") (pintype "passive"))
      (node (ref "R8") (pin "7") (pinfunction "2_7") (pintype "passive"))
    )
    (net (code "31") (name "/c_dq21") (class "Default")
      (node (ref "D1") (pin "J1") (pinfunction "DQ21_J1") (pintype "passive"))
      (node (ref "R8") (pin "6") (pinfunction "2_6") (pintype "passive"))
    )
    (net (code "32") (name "/c_dq22") (class "Default")
      (node (ref "D1") (pin "H2") (pinfunction "DQ22_H2") (pintype "passive"))
      (node (ref "R8") (pin "5") (pinfunction "2_5") (pintype "passive"))
    )
    (net (code "34") (name "/c_dq24") (class "Default")
      (node (ref "D1") (pin "F4") (pinfunction "DQ24_F4") (pintype "passive"))
      (node (ref "R9") (pin "7") (pinfunction "2_7") (pintype "passive"))
    )
    (net (code "35") (name "/c_dq25") (class "Default")
      (node (ref "D1") (pin "G2") (pinfunction "DQ25_G2") (pintype "passive"))
      (node (ref "R10") (pin "8") (pinfunction "2_8") (pintype "passive"))
    )
    (net (code "36") (name "/c_dq26") (class "Default")
      (node (ref "D1") (pin "G3") (pinfunction "DQ26_G3") (pintype "passive"))
      (node (ref "R10") (pin "6") (pinfunction "2_6") (pintype "passive"))
    )
    (net (code "37") (name "/c_dq27") (class "Default")
      (node (ref "D1") (pin "F3") (pinfunction "DQ27_F3") (pintype "passive"))
      (node (ref "R14") (pin "8") (pinfunction "2_8") (pintype "passive"))
    )
    (net (code "38") (name "/c_dq28") (class "Default")
      (node (ref "D1") (pin "F5") (pinfunction "DQ28_F5") (pintype "passive"))
      (node (ref "R17") (pin "6") (pinfunction "2_6") (pintype "passive"))
    )
    (net (code "39") (name "/c_dq29") (class "Default")
      (node (ref "D1") (pin "E1") (pinfunction "DQ29_E1") (pintype "passive"))
    )
    (net (code "40") (name "/c_dq30") (class "Default")
      (node (ref "D1") (pin "E5") (pinfunction "DQ30_E5") (pintype "passive"))
    )
    (net (code "41") (name "/c_dq31") (class "Default")
      (node (ref "D1") (pin "E4") (pinfunction "DQ31_E4") (pintype "passive"))
    )
    (net (code "42") (name "/ctrl0") (class "Default")
      (node (ref "D1") (pin "K8") (pinfunction "CTL0_K8") (pintype "passive"))
      (node (ref "R16") (pin "6") (pinfunction "2_6") (pintype "passive"))
    )
    (net (code "43") (name "/ctrl1") (class "Default")
      (node (ref "D1") (pin "K7") (pinfunction "CTL1_K7") (pintype "passive"))
      (node (ref "R16") (pin "5") (pinfunction "2_5") (pintype "passive"))
    )
    (net (code "44") (name "/ctrl2") (class "Default")
      (node (ref "D1") (pin "J7") (pinfunction "CTL2_J7") (pintype "passive"))
      (node (ref "R17") (pin "8") (pinfunction "2_8") (pintype "passive"))
    )
    (net (code "45") (name "/ctrl3") (class "Default")
      (node (ref "D1") (pin "H7") (pinfunction "CTL3_H7") (pintype "passive"))
      (node (ref "R17") (pin "7") (pinfunction "2_7") (pintype "passive"))
    )
    (net (code "46") (name "/ctrl4") (class "Default")
      (node (ref "D1") (pin "G7") (pinfunction "CTL4_G7") (pintype "passive"))
      (node (ref "R17") (pin "5") (pinfunction "2_5") (pintype "passive"))
    )
    (net (code "47") (name "/ctrl5") (class "Default")
      (node (ref "D1") (pin "G6") (pinfunction "CTL5_G6") (pintype "passive"))
      (node (ref "R18") (pin "8") (pinfunction "2_8") (pintype "passive"))
    )
    (net (code "48") (name "/ctrl6") (class "Default")
      (node (ref "D1") (pin "K6") (pinfunction "CTL6_K6") (pintype "passive"))
      (node (ref "R18") (pin "7") (pinfunction "2_7") (pintype "passive"))
    )
    (net (code "49") (name "/ctrl7") (class "Default")
      (node (ref "D1") (pin "H8") (pinfunction "CTL7_H8") (pintype "passive"))
      (node (ref "R18") (pin "7") (pinfunction "2_7") (pintype "passive"))
    )
    (net (code "50") (name "/ctrl8") (class "Default")
      (node (ref "D1") (pin "G5") (pinfunction "CTL8_G5") (pintype "passive"))
      (node (ref "R18") (pin "5") (pinfunction "2_5") (pintype "passive"))
    )
    (net (code "51") (name "/ctrl9") (class "Default")
      (node (ref "D1") (pin "H6") (pinfunction "CTL9_H6") (pintype "passive"))
      (node (ref "R19") (pin "5") (pinfunction "2_5") (pintype "passive"))
    )
    (net (code "52") (name "/ctrl10") (class "Default")
      (node (ref "D1") (pin "K5") (pinfunction "CTL10_K5") (pintype "passive"))
      (node (ref "R19") (pin "7") (pinfunction "2_7") (pintype "passive"))
    )
    (net (code "53") (name "/ctrl11") (class "Default")
      (node (ref "D1") (pin "J5") (pinfunction "CTL11_J5") (pintype "passive"))
      (node (ref "R19") (pin "6") (pinfunction "2_6") (pintype "passive"))
    )
    (net (code "54") (name "/ctrl12") (class "Default")
      (node (ref "D1") (pin "H5") (pinfunction "CTL12_H5") (pintype "passive"))
      (node (ref "R19") (pin "5") (pinfunction "2_5") (pintype "passive"))
    )
    (net (code "100") (name "/cy_g") (class "Default")
      (node (ref "D1") (pin "D7") (pinfunction "CLKIN_D7") (pintype "passive"))
      (node (ref "VG1") (pin "3") (pinfunction "Out_3") (pintype "passive"))
    )
    (net (code "102") (name "/cy_scl") (class "Default")
      (node (ref "D1") (pin "D9") (pinfunction "I2C-GPIO58_SCL_D9") (pintype "output"))
      (node (ref "D2") (pin "6") (pinfunction "SCL_6") (pintype "input"))
      (node (ref "R20") (pin "1") (pinfunction "1_1") (pintype "passive"))
    )
    (net (code "103") (name "/cy_sda") (class "Default")
      (node (ref "D1") (pin "D10") (pinfunction "I2C-GPIO59_SDA_D10") (pintype "passive"))
      (node (ref "D2") (pin "5") (pinfunction "SDA_5") (pintype "bidirectional"))
      (node (ref "R21") (pin "1") (pinfunction "1_1") (pintype "passive"))
    )
    (net (code "104") (name "/pclk") (class "Default")
      (node (ref "D1") (pin "J6") (pinfunction "PCLK_J6") (pintype "passive"))
      (node (ref "R16") (pin "8") (pinfunction "2_8") (pintype "passive"))
    )
    (net (code "105") (name "/ss_rx_N") (class "Default")
      (node (ref "D1") (pin "A3") (pinfunction "SSRXM_A3") (pintype "passive"))
      (node (ref "X1") (pin "8") (pinfunction "SSRx-_8") (pintype "passive"))
    )
    (net (code "106") (name "/ss_rx_P") (class "Default")
      (node (ref "D1") (pin "A4") (pinfunction "SSRXP_A4") (pintype "passive"))
      (node (ref "X1") (pin "9") (pinfunction "SSRx+_9") (pintype "passive"))
    )
    (net (code "107") (name "/ss_tx_N") (class "Default")
      (node (ref "C3") (pin "1") (pinfunction "1_1") (pintype "passive"))
      (node (ref "X1") (pin "5") (pinfunction "SSTx-_5") (pintype "passive"))
    )
    (net (code "108") (name "/ss_tx_P") (class "Default")
      (node (ref "C2") (pin "1") (pinfunction "1_1") (pintype "passive"))
      (node (ref "X1") (pin "6") (pinfunction "SSTx+_6") (pintype "passive"))
    )
    (net (code "109") (name "/usb_N") (class "Default")
      (node (ref "D1") (pin "A10") (pinfunction "DM_A10") (pintype "passive"))
      (node (ref "X1") (pin "2") (pinfunction "D-_2") (pintype "passive"))
    )
    (net (code "110") (name "/usb_P") (class "Default")
      (node (ref "D1") (pin "A9") (pinfunction "DP_A9") (pintype "passive"))
      (node (ref "X1") (pin "3") (pinfunction "D+_3") (pintype "passive"))
    )
    (net (code "111") (name "/v1p2d") (class "Default")
      (node (ref "C14") (pin "2") (pinfunction "2_2") (pintype "passive"))
      (node (ref "C15") (pin "2") (pinfunction "2_2") (pintype "passive"))
      (node (ref "C16") (pin "2") (pinfunction "2_2") (pintype "passive"))
      (node (ref "C17") (pin "2") (pinfunction "2_2") (pintype "passive"))
      (node (ref "C18") (pin "2") (pinfunction "2_2") (pintype "passive"))
      (node (ref "C19") (pin "2") (pinfunction "2_2") (pintype "passive"))
      (node (ref "C20") (pin "2") (pinfunction "2_2") (pintype "passive"))
      (node (ref "C21") (pin "2") (pinfunction "2_2") (pintype "passive"))
      (node (ref "C22") (pin "2") (pinfunction "2_2") (pintype "passive"))
      (node (ref "C23") (pin "2") (pinfunction "2_2") (pintype "passive"))
      (node (ref "C6") (pin "2") (pinfunction "2_2") (pintype "passive"))
      (node (ref "D1") (pin "B10") (pinfunction "VDD_EFVDDQ_B10") (pintype "passive"))
      (node (ref "D1") (pin "C3") (pinfunction "VDD2_C3") (pintype "passive"))
      (node (ref "D1") (pin "E9") (pinfunction "VDD4_E9") (pintype "passive"))
      (node (ref "D1") (pin "F11") (pinfunction "VDD5_F11") (pintype "passive"))
      (node (ref "D1") (pin "H1") (pinfunction "VDD1_H1") (pintype "passive"))
      (node (ref "D1") (pin "J11") (pinfunction "VDD_SRAM_VDD2_J11") (pintype "passive"))
      (node (ref "D1") (pin "L5") (pinfunction "VDD_SRAM_VDD1_L5") (pintype "passive"))
      (node (ref "D1") (pin "L7") (pinfunction "VDD3_L7") (pintype "passive"))
      (node (ref "D3") (pin "10") (pinfunction "Vout_10") (pintype "passive"))
      (node (ref "D3") (pin "11") (pinfunction "Vout_11") (pintype "passive"))
      (node (ref "D3") (pin "12") (pinfunction "Vout_12") (pintype "passive"))
      (node (ref "D3") (pin "13") (pinfunction "Vout_13") (pintype "passive"))
      (node (ref "D3") (pin "14") (pinfunction "Vout_14") (pintype "passive"))
      (node (ref "L1") (pin "1") (pinfunction "1_1") (pintype "passive"))
      (node (ref "L2") (pin "1") (pinfunction "1_1") (pintype "passive"))
      (node (ref "L3") (pin "1") (pinfunction "1_1") (pintype "passive"))
      (node (ref "R27") (pin "2") (pinfunction "2_2") (pintype "passive"))
    )
    (net (code "112") (name "/v1p8d") (class "Default")
      (node (ref "C24") (pin "2") (pinfunction "2_2") (pintype "passive"))
      (node (ref "C25") (pin "2") (pinfunction "2_2") (pintype "passive"))
      (node (ref "C26") (pin "2") (pinfunction "2_2") (pintype "passive"))
      (node (ref "C27") (pin "2") (pinfunction "2_2") (pintype "passive"))
      (node (ref "C28") (pin "2") (pinfunction "2_2") (pintype "passive"))
      (node (ref "C29") (pin "2") (pinfunction "2_2") (pintype "passive"))
      (node (ref "C30") (pin "2") (pinfunction "2_2") (pintype "passive"))
      (node (ref "D1") (pin "B1") (pinfunction "VIO4_B1") (pintype "passive"))
      (node (ref "D1") (pin "E3") (pinfunction "VIO3_E3") (pintype "passive"))
      (node (ref "D1") (pin "F1") (pinfunction "VIO2_F1") (pintype "passive"))
      (node (ref "D1") (pin "H11") (pinfunction "VIO1_2_H11") (pintype "passive"))
      (node (ref "D1") (pin "L9") (pinfunction "VIO1_1_L9") (pintype "passive"))
      (node (ref "D3") (pin "1") (pinfunction "Vin_1") (pintype "passive"))
      (node (ref "D3") (pin "15") (pinfunction "Vin_15") (pintype "passive"))
      (node (ref "D3") (pin "16") (pinfunction "Vin_16") (pintype "passive"))
      (node (ref "D3") (pin "2") (pinfunction "Vin_2") (pintype "passive"))
      (node (ref "D3") (pin "3") (pinfunction "Vin_3") (pintype "passive"))
      (node (ref "D3") (pin "4") (pinfunction "EN_4") (pintype "passive"))
      (node (ref "R22") (pin "2") (pinfunction "2_2") (pintype "passive"))
      (node (ref "R23") (pin "2") (pinfunction "2_2") (pintype "passive"))
      (node (ref "R26") (pin "2") (pinfunction "2_2") (pintype "passive"))
      (node (ref "R30") (pin "2") (pinfunction "2_2") (pintype "passive"))
    )
    (net (code "113") (name "/v3p3d") (class "Default")
      (node (ref "C31") (pin "2") (pinfunction "2_2") (pintype "passive"))
      (node (ref "C32") (pin "2") (pinfunction "2_2") (pintype "passive"))
      (node (ref "C33") (pin "2") (pinfunction "2_2") (pintype "passive"))
      (node (ref "C34") (pin "2") (pinfunction "2_2") (pintype "passive"))
      (node (ref "C35") (pin "2") (pinfunction "2_2") (pintype "passive"))
      (node (ref "C36") (pin "2") (pinfunction "2_2") (pintype "passive"))
      (node (ref "D1") (pin "B6") (pinfunction "CVDDQ_B6") (pintype "passive"))
      (node (ref "D1") (pin "C11") (pinfunction "VIO5_C11") (pintype "passive"))
      (node (ref "D1") (pin "E10") (pinfunction "VBAT_E10") (pintype "passive"))
      (node (ref "D2") (pin "8") (pinfunction "VCC_8") (pintype "power_in"))
      (node (ref "R11") (pin "1") (pinfunction "1_1") (pintype "passive"))
      (node (ref "R20") (pin "2") (pinfunction "2_2") (pintype "passive"))
      (node (ref "R21") (pin "2") (pinfunction "2_2") (pintype "passive"))
      (node (ref "R7") (pin "1") (pinfunction "1_1") (pintype "passive"))
      (node (ref "VG1") (pin "4") (pinfunction "Vcc_4") (pintype "passive"))
    )
    (net (code "114") (name "Net-(D1A-INT_N_CTL15)") (class "Default")
      (node (ref "D1") (pin "L8") (pinfunction "INT_N_CTL15_L8") (pintype "passive"))
      (node (ref "R25") (pin "1") (pinfunction "1_1") (pintype "passive"))
    )
    (net (code "115") (name "Net-(D1A-PMODE0)") (class "Default")
      (node (ref "D1") (pin "G4") (pinfunction "PMODE0_G4") (pintype "passive"))
      (node (ref "R22") (pin "1") (pinfunction "1_1") (pintype "passive"))
    )
    (net (code "116") (name "Net-(D1A-PMODE1)") (class "Default")
      (node (ref "D1") (pin "H4") (pinfunction "PMODE1_H4") (pintype "passive"))
      (node (ref "R23") (pin "1") (pinfunction "1_1") (pintype "passive"))
    )
    (net (code "117") (name "Net-(D1A-PMODE2)") (class "Default")
      (node (ref "D1") (pin "L4") (pinfunction "PMODE2_L4") (pintype "passive"))
      (node (ref "R24") (pin "1") (pinfunction "1_1") (pintype "passive"))
    )
    (net (code "118") (name "Net-(D1A-RESET_N)") (class "Default")
      (node (ref "C9") (pin "2") (pinfunction "2_2") (pintype "passive"))
      (node (ref "D1") (pin "C5") (pinfunction "RESET_N_C5") (pintype "passive"))
      (node (ref "R26") (pin "1") (pinfunction "1_1") (pintype "passive"))
    )
    (net (code "119") (name "Net-(D1D-OTG_ID)") (class "Default")
      (node (ref "D1") (pin "C9") (pinfunction "OTG_ID_C9") (pintype "passive"))
      (node (ref "R4") (pin "1") (pinfunction "1_1") (pintype "passive"))
    )
    (net (code "120") (name "Net-(D1D-R_USB2)") (class "Default")
      (node (ref "D1") (pin "C8") (pinfunction "R_USB2_C8") (pintype "passive"))
      (node (ref "R12") (pin "1") (pinfunction "1_1") (pintype "passive"))
    )
    (net (code "121") (name "Net-(D1D-R_USB3)") (class "Default")
      (node (ref "D1") (pin "B3") (pinfunction "R_USB3_B3") (pintype "passive"))
      (node (ref "R13") (pin "1") (pinfunction "1_1") (pintype "passive"))
    )
    (net (code "122") (name "Net-(D1D-SSTXM)") (class "Default")
      (node (ref "C3") (pin "2") (pinfunction "2_2") (pintype "passive"))
      (node (ref "D1") (pin "A6") (pinfunction "SSTXM_A6") (pintype "passive"))
    )
    (net (code "123") (name "Net-(D1D-SSTXP)") (class "Default")
      (node (ref "C2") (pin "2") (pinfunction "2_2") (pintype "passive"))
      (node (ref "D1") (pin "A5") (pinfunction "SSTXP_A5") (pintype "passive"))
    )
    (net (code "124") (name "Net-(D1D-VBUS)") (class "Default")
      (node (ref "C1") (pin "1") (pinfunction "1_1") (pintype "passive"))
      (node (ref "D1") (pin "E11") (pinfunction "VBUS_E11") (pintype "passive"))
      (node (ref "R1") (pin "1") (pinfunction "1_1") (pintype "passive"))
    )
    (net (code "125") (name "Net-(D1E-FSLC0)") (class "Default")
      (node (ref "D1") (pin "B2") (pinfunction "FSLC0_B2") (pintype "passive"))
      (node (ref "R3") (pin "2") (pinfunction "2_2") (pintype "passive"))
    )
    (net (code "126") (name "Net-(D1E-FSLC1)") (class "Default")
      (node (ref "D1") (pin "B4") (pinfunction "FSLC1_B4") (pintype "passive"))
      (node (ref "R5") (pin "2") (pinfunction "2_2") (pintype "passive"))
    )
    (net (code "127") (name "Net-(D1E-FSLC2)") (class "Default")
      (node (ref "D1") (pin "E6") (pinfunction "FSLC2_E6") (pintype "passive"))
      (node (ref "R7") (pin "2") (pinfunction "2_2") (pintype "passive"))
    )
    (net (code "128") (name "Net-(D1E-XTALIN)") (class "Default")
      (node (ref "C5") (pin "2") (pinfunction "2_2") (pintype "passive"))
      (node (ref "D1") (pin "C6") (pinfunction "XTALIN_C6") (pintype "passive"))
      (node (ref "ZQ1") (pin "2") (pinfunction "2_2") (pintype "passive"))
    )
    (net (code "129") (name "Net-(D1E-XTALOUT)") (class "Default")
      (node (ref "C4") (pin "2") (pinfunction "2_2") (pintype "passive"))
      (node (ref "D1") (pin "C7") (pinfunction "XTALOUT_C7") (pintype "passive"))
      (node (ref "ZQ1") (pin "1") (pinfunction "1_1") (pintype "passive"))
    )
    (net (code "130") (name "Net-(D3-Adj)") (class "Default")
      (node (ref "D3") (pin "9") (pinfunction "Adj_9") (pintype "passive"))
      (node (ref "R27") (pin "1") (pinfunction "1_1") (pintype "passive"))
      (node (ref "R29") (pin "2") (pinfunction "2_2") (pintype "passive"))
    )
    (net (code "131") (name "Net-(D3-PG)") (class "Default")
      (node (ref "D3") (pin "5") (pinfunction "PG_5") (pintype "passive"))
      (node (ref "R30") (pin "1") (pinfunction "1_1") (pintype "passive"))
    )
    (net (code "132") (name "Net-(VG1-EN)") (class "Default")
      (node (ref "R11") (pin "2") (pinfunction "2_2") (pintype "passive"))
      (node (ref "VG1") (pin "1") (pinfunction "EN_1") (pintype "passive"))
    )
    (net (code "133") (name "Net-(X1-VBUS)") (class "Default")
      (node (ref "R1") (pin "2") (pinfunction "2_2") (pintype "passive"))
      (node (ref "X1") (pin "1") (pinfunction "VBUS_1") (pintype "passive"))
    )
    (net (code "134") (name "unconnected-(D1B-DQ23-PadH3)") (class "Default")
      (node (ref "D1") (pin "H3") (pinfunction "DQ23_H3") (pintype "passive"))
    )
    (net (code "135") (name "unconnected-(D1B-GPIO45-PadF2)") (class "Default")
      (node (ref "D1") (pin "F2") (pinfunction "GPIO45_F2") (pintype "passive"))
    )
    (net (code "136") (name "unconnected-(D1C-I2S-CLK-PadD1)") (class "Default")
      (node (ref "D1") (pin "D1") (pinfunction "I2S-CLK_D1") (pintype "passive"))
    )
    (net (code "137") (name "unconnected-(D1C-I2S-MCLK-PadC4)") (class "Default")
      (node (ref "D1") (pin "C4") (pinfunction "I2S-MCLK_C4") (pintype "passive"))
    )
    (net (code "138") (name "unconnected-(D1C-UART-TX_SPI-MISO-PadC2)") (class "Default")
      (node (ref "D1") (pin "C2") (pinfunction "UART-TX_SPI-MISO_C2") (pintype "passive"))
    )
    (net (code "139") (name "unconnected-(D1D-NC-PadA11)") (class "Default")
      (node (ref "D1") (pin "A11") (pinfunction "NC_A11") (pintype "passive"))
    )
    (net (code "140") (name "unconnected-(D1E-CLKIN_32-PadD6)") (class "Default")
      (node (ref "D1") (pin "D6") (pinfunction "CLKIN_32_D6") (pintype "passive"))
    )
    (net (code "141") (name "unconnected-(D1F-I2C-GPIO60_CHARGER-DETECT-PadD11)") (class "Default")
      (node (ref "D1") (pin "D11") (pinfunction "I2C-GPIO60_CHARGER-DETECT_D11") (pintype "passive"))
    )
    (net (code "142") (name "unconnected-(D1F-TCK-PadF6)") (class "Default")
      (node (ref "D1") (pin "F6") (pinfunction "TCK_F6") (pintype "passive"))
    )
    (net (code "143") (name "unconnected-(D1F-TDI-PadE7)") (class "Default")
      (node (ref "D1") (pin "E7") (pinfunction "TDI_E7") (pintype "passive"))
    )
    (net (code "144") (name "unconnected-(D1F-TDO-PadC10)") (class "Default")
      (node (ref "D1") (pin "C10") (pinfunction "TDO_C10") (pintype "passive"))
    )
    (net (code "145") (name "unconnected-(D1F-TMS-PadE8)") (class "Default")
      (node (ref "D1") (pin "E8") (pinfunction "TMS_E8") (pintype "passive"))
    )
    (net (code "146") (name "unconnected-(D1F-TRST_N-PadB11)") (class "Default")
      (node (ref "D1") (pin "B11") (pinfunction "TRST_N_B11") (pintype "passive"))
    )
    (net (code "147") (name "unconnected-(D3-NC-Pad8)") (class "Default")
      (node (ref "D3") (pin "8") (pinfunction "NC_8") (pintype "passive"))
    )
    (net (code "148") (name "unconnected-(D3-SS-Pad7)") (class "Default")
      (node (ref "D3") (pin "7") (pinfunction "SS_7") (pintype "passive"))
    )
    (net (code "149") (name "unconnected-(R2-Pad1)") (class "Default")
      (node (ref "R2") (pin "1") (pinfunction "1_1") (pintype "passive"))
    )
    (net (code "150") (name "unconnected-(R2B-1-Pad2)") (class "Default")
      (node (ref "R2") (pin "2") (pinfunction "1_2") (pintype "passive"))
    )
    (net (code "151") (name "unconnected-(R2C-1-Pad3)") (class "Default")
      (node (ref "R2") (pin "3") (pinfunction "1_3") (pintype "passive"))
    )
    (net (code "152") (name "unconnected-(R2D-1-Pad4)") (class "Default")
      (node (ref "R2") (pin "4") (pinfunction "1_4") (pintype "passive"))
    )
    (net (code "153") (name "unconnected-(R6-Pad1)") (class "Default")
      (node (ref "R6") (pin "1") (pinfunction "1_1") (pintype "passive"))
    )
    (net (code "154") (name "unconnected-(R6B-1-Pad2)") (class "Default")
      (node (ref "R6") (pin "2") (pinfunction "1_2") (pintype "passive"))
    )
    (net (code "155") (name "unconnected-(R6C-1-Pad3)") (class "Default")
      (node (ref "R6") (pin "3") (pinfunction "1_3") (pintype "passive"))
    )
    (net (code "156") (name "unconnected-(R6D-1-Pad4)") (class "Default")
      (node (ref "R6") (pin "4") (pinfunction "1_4") (pintype "passive"))
    )
    (net (code "157") (name "unconnected-(R8-Pad1)") (class "Default")
      (node (ref "R8") (pin "1") (pinfunction "1_1") (pintype "passive"))
    )
    (net (code "158") (name "unconnected-(R8B-1-Pad2)") (class "Default")
      (node (ref "R8") (pin "2") (pinfunction "1_2") (pintype "passive"))
    )
    (net (code "159") (name "unconnected-(R8C-1-Pad3)") (class "Default")
      (node (ref "R8") (pin "3") (pinfunction "1_3") (pintype "passive"))
    )
    (net (code "160") (name "unconnected-(R8D-1-Pad4)") (class "Default")
      (node (ref "R8") (pin "4") (pinfunction "1_4") (pintype "passive"))
    )
    (net (code "161") (name "unconnected-(R9-Pad1)") (class "Default")
      (node (ref "R9") (pin "1") (pinfunction "1_1") (pintype "passive"))
    )
    (net (code "162") (name "unconnected-(R9B-1-Pad2)") (class "Default")
      (node (ref "R9") (pin "2") (pinfunction "1_2") (pintype "passive"))
    )
    (net (code "163") (name "unconnected-(R9C-1-Pad3)") (class "Default")
      (node (ref "R9") (pin "3") (pinfunction "1_3") (pintype "passive"))
    )
    (net (code "164") (name "unconnected-(R9D-1-Pad4)") (class "Default")
      (node (ref "R9") (pin "4") (pinfunction "1_4") (pintype "passive"))
    )
    (net (code "165") (name "unconnected-(R10-Pad1)") (class "Default")
      (node (ref "R10") (pin "1") (pinfunction "1_1") (pintype "passive"))
    )
    (net (code "166") (name "unconnected-(R10B-1-Pad2)") (class "Default")
      (node (ref "R10") (pin "2") (pinfunction "1_2") (pintype "passive"))
    )
    (net (code "167") (name "unconnected-(R10C-1-Pad3)") (class "Default")
      (node (ref "R10") (pin "3") (pinfunction "1_3") (pintype "passive"))
    )
    (net (code "168") (name "unconnected-(R10D-1-Pad4)") (class "Default")
      (node (ref "R10") (pin "4") (pinfunction "1_4") (pintype "passive"))
    )
    (net (code "169") (name "unconnected-(R14-Pad1)") (class "Default")
      (node (ref "R14") (pin "1") (pinfunction "1_1") (pintype "passive"))
    )
    (net (code "170") (name "unconnected-(R14B-1-Pad2)") (class "Default")
      (node (ref "R14") (pin "2") (pinfunction "1_2") (pintype "passive"))
    )
    (net (code "171") (name "unconnected-(R14C-1-Pad3)") (class "Default")
      (node (ref "R14") (pin "3") (pinfunction "1_3") (pintype "passive"))
    )
    (net (code "172") (name "unconnected-(R14D-1-Pad4)") (class "Default")
      (node (ref "R14") (pin "4") (pinfunction "1_4") (pintype "passive"))
    )
    (net (code "173") (name "unconnected-(R14D-2-Pad5)") (class "Default")
      (node (ref "R14") (pin "5") (pinfunction "2_5") (pintype "passive"))
    )
    (net (code "174") (name "unconnected-(R15-Pad1)") (class "Default")
      (node (ref "R15") (pin "1") (pinfunction "1_1") (pintype "passive"))
    )
    (net (code "175") (name "unconnected-(R15B-1-Pad2)") (class "Default")
      (node (ref "R15") (pin "2") (pinfunction "1_2") (pintype "passive"))
    )
    (net (code "176") (name "unconnected-(R15B-2-Pad7)") (class "Default")
      (node (ref "R15") (pin "7") (pinfunction "2_7") (pintype "passive"))
    )
    (net (code "177") (name "unconnected-(R15C-1-Pad3)") (class "Default")
      (node (ref "R15") (pin "3") (pinfunction "1_3") (pintype "passive"))
    )
    (net (code "178") (name "unconnected-(R15D-1-Pad4)") (class "Default")
      (node (ref "R15") (pin "4") (pinfunction "1_4") (pintype "passive"))
    )
    (net (code "179") (name "unconnected-(R15D-2-Pad5)") (class "Default")
      (node (ref "R15") (pin "5") (pinfunction "2_5") (pintype "passive"))
    )
    (net (code "180") (name "unconnected-(R16-Pad1)") (class "Default")
      (node (ref "R16") (pin "1") (pinfunction "1_1") (pintype "passive"))
    )
    (net (code "181") (name "unconnected-(R16B-1-Pad2)") (class "Default")
      (node (ref "R16") (pin "2") (pinfunction "1_2") (pintype "passive"))
    )
    (net (code "182") (name "unconnected-(R16B-2-Pad7)") (class "Default")
      (node (ref "R16") (pin "7") (pinfunction "2_7") (pintype "passive"))
    )
    (net (code "183") (name "unconnected-(R16C-1-Pad3)") (class "Default")
      (node (ref "R16") (pin "3") (pinfunction "1_3") (pintype "passive"))
    )
    (net (code "184") (name "unconnected-(R16D-1-Pad4)") (class "Default")
      (node (ref "R16") (pin "4") (pinfunction "1_4") (pintype "passive"))
    )
    (net (code "185") (name "unconnected-(R17-Pad1)") (class "Default")
      (node (ref "R17") (pin "1") (pinfunction "1_1") (pintype "passive"))
    )
    (net (code "186") (name "unconnected-(R17B-1-Pad2)") (class "Default")
      (node (ref "R17") (pin "2") (pinfunction "1_2") (pintype "passive"))
    )
    (net (code "187") (name "unconnected-(R17C-1-Pad3)") (class "Default")
      (node (ref "R17") (pin "3") (pinfunction "1_3") (pintype "passive"))
    )
    (net (code "188") (name "unconnected-(R17D-1-Pad4)") (class "Default")
      (node (ref "R17") (pin "4") (pinfunction "1_4") (pintype "passive"))
    )
    (net (code "189") (name "unconnected-(R18-Pad1)") (class "Default")
      (node (ref "R18") (pin "1") (pinfunction "1_1") (pintype "passive"))
    )
    (net (code "190") (name "unconnected-(R18B-1-Pad2)") (class "Default")
      (node (ref "R18") (pin "2") (pinfunction "1_2") (pintype "passive"))
    )
    (net (code "191") (name "unconnected-(R18C-1-Pad3)") (class "Default")
      (node (ref "R18") (pin "3") (pinfunction "1_3") (pintype "passive"))
    )
    (net (code "192") (name "unconnected-(R18D-1-Pad4)") (class "Default")
      (node (ref "R18") (pin "4") (pinfunction "1_4") (pintype "passive"))
    )
    (net (code "193") (name "unconnected-(R19-Pad1)") (class "Default")
      (node (ref "R19") (pin "1") (pinfunction "1_1") (pintype "passive"))
    )
    (net (code "194") (name "unconnected-(R19B-1-Pad2)") (class "Default")
      (node (ref "R19") (pin "2") (pinfunction "1_2") (pintype "passive"))
    )
    (net (code "195") (name "unconnected-(R19C-1-Pad3)") (class "Default")
      (node (ref "R19") (pin "3") (pinfunction "1_3") (pintype "passive"))
    )
    (net (code "196") (name "unconnected-(R19D-1-Pad4)") (class "Default")
      (node (ref "R19") (pin "4") (pinfunction "1_4") (pintype "passive"))
    )
    (net (code "197") (name "unconnected-(R28-Pad1)") (class "Default")
      (node (ref "R28") (pin "1") (pinfunction "1_1") (pintype "passive"))
    )
    (net (code "198") (name "unconnected-(R28A-2-Pad8)") (class "Default")
      (node (ref "R28") (pin "8") (pinfunction "2_8") (pintype "passive"))
    )
    (net (code "199") (name "unconnected-(R28B-1-Pad2)") (class "Default")
      (node (ref "R28") (pin "2") (pinfunction "1_2") (pintype "passive"))
    )
    (net (code "200") (name "unconnected-(R28B-2-Pad7)") (class "Default")
      (node (ref "R28") (pin "7") (pinfunction "2_7") (pintype "passive"))
    )
    (net (code "201") (name "unconnected-(R28C-1-Pad3)") (class "Default")
      (node (ref "R28") (pin "3") (pinfunction "1_3") (pintype "passive"))
    )
    (net (code "202") (name "unconnected-(R28C-2-Pad6)") (class "Default")
      (node (ref "R28") (pin "6") (pinfunction "2_6") (pintype "passive"))
    )
    (net (code "203") (name "unconnected-(R28D-1-Pad4)") (class "Default")
      (node (ref "R28") (pin "4") (pinfunction "1_4") (pintype "passive"))
    )
    (net (code "204") (name "unconnected-(R28D-2-Pad5)") (class "Default")
      (node (ref "R28") (pin "5") (pinfunction "2_5") (pintype "passive"))
    )
  )
)
